# 1-Schematic_Rotopano.net
KiCad netlist of a schematic drawn in EasyEDA
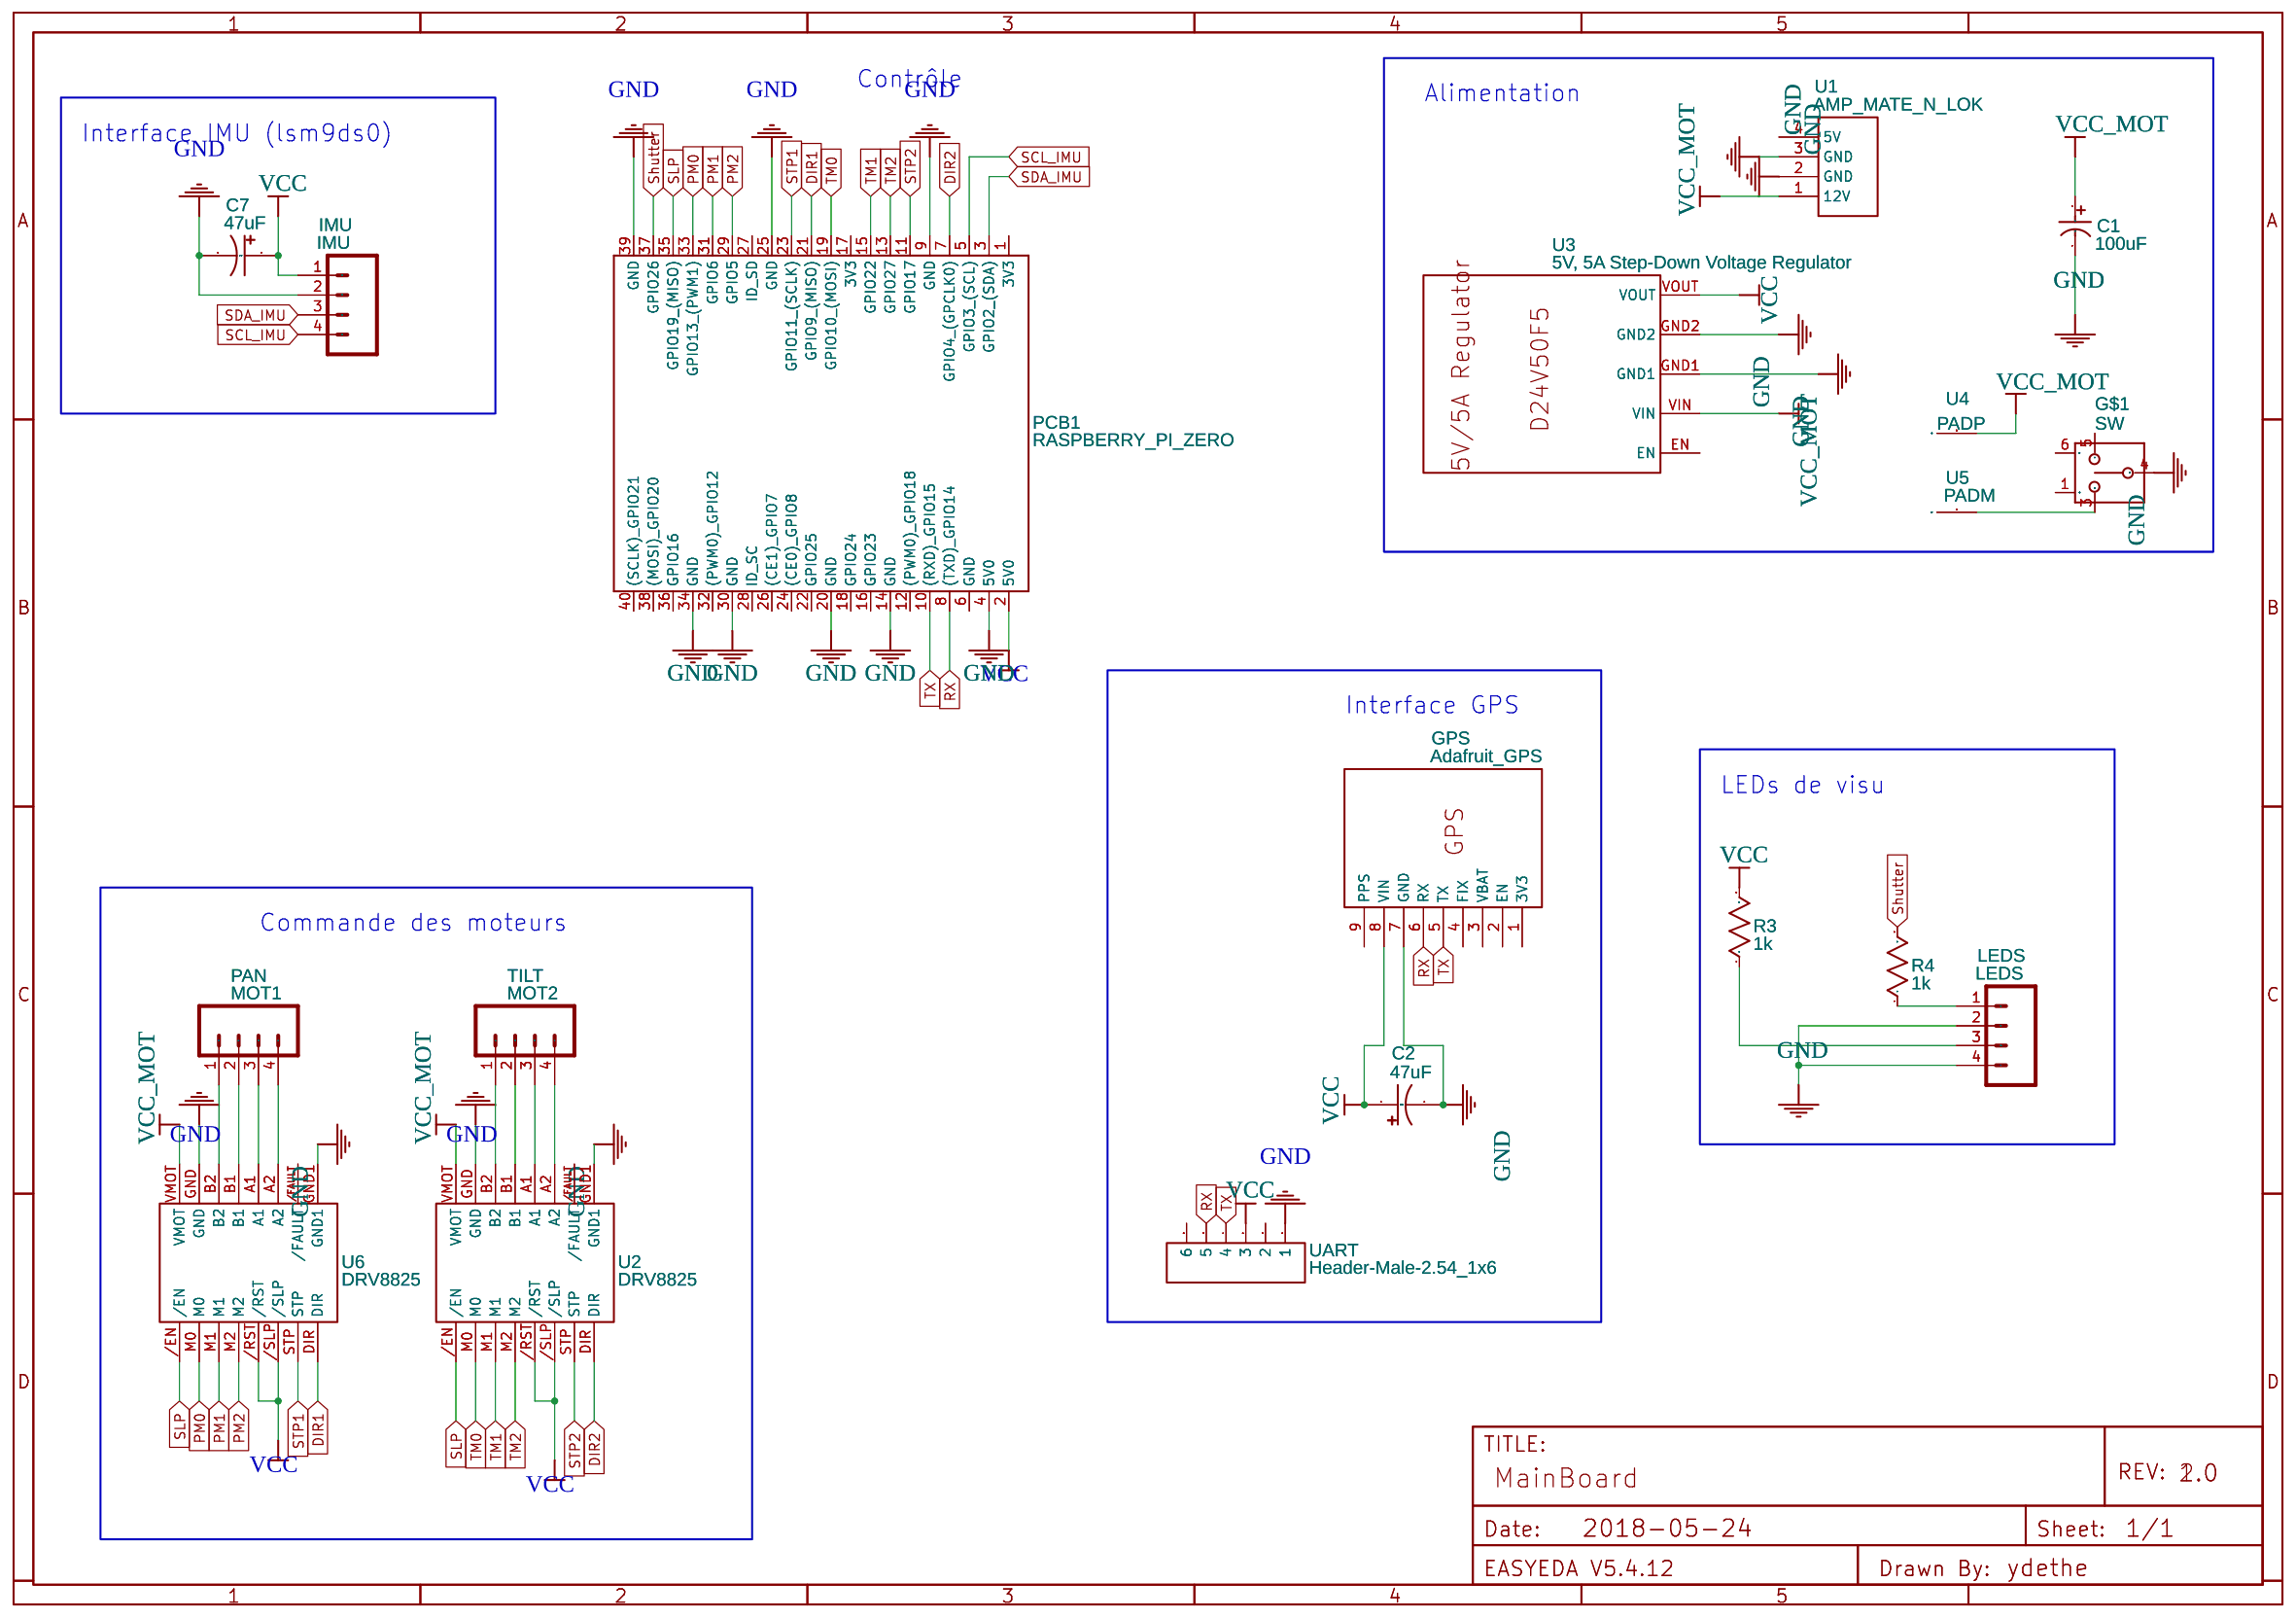
[diagram p0: schematic sheet]

(export (version "E")
  (design (tool "Eeschema 10.0.6"))
  (components
    (comp (ref "C1")
      (value "100uF")
      (fields (field (name "BOM_Manufacturer Part") "100uF 25V") (field (name "BOM_Supplier Part") "C13376"))
      (libsource (lib "") (part "100uF 25V"))
    )
    (comp (ref "C2")
      (value "47uF")
      (fields (field (name "BOM_Manufacturer Part") "?"))
      (libsource (lib "") (part "Cap_Electrolytic(TH)_D6.3XF2.5_US_1"))
    )
    (comp (ref "C7")
      (value "47uF")
      (fields (field (name "BOM_Manufacturer Part") "?"))
      (libsource (lib "") (part "Cap_Electrolytic(TH)_D6.3XF2.5_US"))
    )
    (comp (ref "G$1")
      (value "SW")
      (fields (field (name "BOM_Manufacturer Part") "?"))
      (libsource (lib "") (part "Unknown_840_20"))
    )
    (comp (ref "GPS")
      (value "Adafruit_GPS")
      (fields
        (field (name "BOM_Manufacturer Part") "Adafruit Ultimate GPS Breakout - 66 channel w/10 Hz updates - Version 3")
        (field (name "BOM_Supplier Part") "undefined")
      )
      (libsource (lib "") (part "Unknown_550_180"))
    )
    (comp (ref "IMU")
      (value "IMU")
      (fields (field (name "BOM_Manufacturer Part") "?"))
      (libsource (lib "") (part "Unknown_-50_-60"))
    )
    (comp (ref "LEDS")
      (value "LEDS")
      (fields (field (name "BOM_Manufacturer Part") "?"))
      (libsource (lib "") (part "Unknown_790_310"))
    )
    (comp (ref "PAN")
      (value "MOT1")
      (fields (field (name "BOM_Manufacturer Part") "?"))
      (libsource (lib "") (part "Unknown_-100_320"))
    )
    (comp (ref "PCB1")
      (value "RASPBERRY_PI_ZERO")
      (fields (field (name "BOM_Manufacturer Part") "?"))
      (libsource (lib "") (part "Unknown_200_10"))
    )
    (comp (ref "R3")
      (value "1k")
      (fields (field (name "BOM_Manufacturer Part") "?"))
      (libsource (lib "") (part "Res_AXIAL-0.3(1/8W)_US"))
    )
    (comp (ref "R4")
      (value "1k")
      (fields (field (name "BOM_Manufacturer Part") "?"))
      (libsource (lib "") (part "Res_AXIAL-0.3(1/8W)_US"))
    )
    (comp (ref "TILT")
      (value "MOT2")
      (fields (field (name "BOM_Manufacturer Part") "?"))
      (libsource (lib "") (part "Unknown_40_320"))
    )
    (comp (ref "U1")
      (value "AMP_MATE_N_LOK")
      (fields (field (name "BOM_Manufacturer Part") "350424-1") (field (name "BOM_Supplier Part") "718-9605"))
      (libsource (lib "") (part "Unknown_720_-110"))
    )
    (comp (ref "U2")
      (value "DRV8825")
      (fields (field (name "BOM_Manufacturer Part") "Pololu") (field (name "BOM_Supplier Part") "undefined"))
      (libsource (lib "") (part "Unknown_0_460"))
    )
    (comp (ref "U3")
      (value "5V, 5A Step-Down Voltage Regulator")
      (fields (field (name "BOM_Manufacturer Part") "D24V50F5"))
      (libsource (lib "") (part "Unknown_490_40"))
    )
    (comp (ref "U4")
      (value "PADP")
      (fields (field (name "BOM_Manufacturer Part") "?"))
      (libsource (lib "") (part "Unknown_760_10"))
    )
    (comp (ref "U5")
      (value "PADM")
      (fields (field (name "BOM_Manufacturer Part") "?"))
      (libsource (lib "") (part "Unknown_760_50"))
    )
    (comp (ref "U6")
      (value "DRV8825")
      (fields (field (name "BOM_Manufacturer Part") "Pololu") (field (name "BOM_Supplier Part") "undefined"))
      (libsource (lib "") (part "Unknown_-140_460"))
    )
    (comp (ref "UART")
      (value "Header-Male-2.54_1x6")
      (fields (field (name "BOM_Supplier Part") "C37208"))
      (libsource (lib "") (part "Unknown_400_430"))
    )
  )
  (nets
    (net (code "1") (name "DIR1") (class "Default")
      (node (ref "PCB1") (pin "21") (pinfunction "GPIO9_(MISO)_21") (pintype "unspecified"))
      (node (ref "U6") (pin "DIR") (pinfunction "DIR_DIR") (pintype "unspecified"))
    )
    (net (code "2") (name "DIR2") (class "Default")
      (node (ref "PCB1") (pin "7") (pinfunction "GPIO4_(GPCLK0)_7") (pintype "unspecified"))
      (node (ref "U2") (pin "DIR") (pinfunction "DIR_DIR") (pintype "unspecified"))
    )
    (net (code "3") (name "GND") (class "Default")
      (node (ref "C1") (pin "2") (pinfunction "2_2") (pintype "input"))
      (node (ref "C2") (pin "2") (pinfunction "2_2") (pintype "unspecified"))
      (node (ref "C7") (pin "2") (pinfunction "2_2") (pintype "unspecified"))
      (node (ref "G$1") (pin "4") (pinfunction "2_4") (pintype "bidirectional"))
      (node (ref "GPS") (pin "7") (pinfunction "GND_7") (pintype "unspecified"))
      (node (ref "IMU") (pin "2") (pinfunction "2_2") (pintype "unspecified"))
      (node (ref "LEDS") (pin "2") (pinfunction "2_2") (pintype "unspecified"))
      (node (ref "LEDS") (pin "4") (pinfunction "4_4") (pintype "unspecified"))
      (node (ref "PCB1") (pin "14") (pinfunction "GND_14") (pintype "unspecified"))
      (node (ref "PCB1") (pin "20") (pinfunction "GND_20") (pintype "unspecified"))
      (node (ref "PCB1") (pin "25") (pinfunction "GND_25") (pintype "unspecified"))
      (node (ref "PCB1") (pin "30") (pinfunction "GND_30") (pintype "unspecified"))
      (node (ref "PCB1") (pin "34") (pinfunction "GND_34") (pintype "unspecified"))
      (node (ref "PCB1") (pin "39") (pinfunction "GND_39") (pintype "unspecified"))
      (node (ref "PCB1") (pin "4") (pinfunction "5V0_4") (pintype "unspecified"))
      (node (ref "PCB1") (pin "9") (pinfunction "GND_9") (pintype "unspecified"))
      (node (ref "U1") (pin "2") (pinfunction "GND_2") (pintype "unspecified"))
      (node (ref "U1") (pin "3") (pinfunction "GND_3") (pintype "unspecified"))
      (node (ref "U2") (pin "GND") (pinfunction "GND_GND") (pintype "unspecified"))
      (node (ref "U2") (pin "GND1") (pinfunction "GND1_GND1") (pintype "unspecified"))
      (node (ref "U3") (pin "GND1") (pinfunction "GND1_GND1") (pintype "unspecified"))
      (node (ref "U3") (pin "GND2") (pinfunction "GND2_GND2") (pintype "unspecified"))
      (node (ref "U6") (pin "GND") (pinfunction "GND_GND") (pintype "unspecified"))
      (node (ref "U6") (pin "GND1") (pinfunction "GND1_GND1") (pintype "unspecified"))
      (node (ref "UART") (pin "1") (pinfunction "1_1") (pintype "input"))
    )
    (net (code "4") (name "Net-(G$1-Pad3)") (class "Default")
      (node (ref "G$1") (pin "3") (pinfunction "3_3") (pintype "bidirectional"))
      (node (ref "U5") (pin "P$1") (pinfunction "P$1_P$1") (pintype "unspecified"))
    )
    (net (code "5") (name "Net-(LEDS-Pad1)") (class "Default")
      (node (ref "LEDS") (pin "1") (pinfunction "1_1") (pintype "unspecified"))
      (node (ref "R4") (pin "1") (pinfunction "1_1") (pintype "unspecified"))
    )
    (net (code "6") (name "Net-(LEDS-Pad3)") (class "Default")
      (node (ref "LEDS") (pin "3") (pinfunction "3_3") (pintype "unspecified"))
      (node (ref "R3") (pin "1") (pinfunction "1_1") (pintype "unspecified"))
    )
    (net (code "7") (name "Net-(PAN-Pad1)") (class "Default")
      (node (ref "PAN") (pin "1") (pinfunction "1_1") (pintype "unspecified"))
      (node (ref "U6") (pin "B2") (pinfunction "B2_B2") (pintype "unspecified"))
    )
    (net (code "8") (name "Net-(PAN-Pad2)") (class "Default")
      (node (ref "PAN") (pin "2") (pinfunction "2_2") (pintype "unspecified"))
      (node (ref "U6") (pin "B1") (pinfunction "B1_B1") (pintype "unspecified"))
    )
    (net (code "9") (name "Net-(PAN-Pad3)") (class "Default")
      (node (ref "PAN") (pin "3") (pinfunction "3_3") (pintype "unspecified"))
      (node (ref "U6") (pin "A1") (pinfunction "A1_A1") (pintype "unspecified"))
    )
    (net (code "10") (name "Net-(PAN-Pad4)") (class "Default")
      (node (ref "PAN") (pin "4") (pinfunction "4_4") (pintype "unspecified"))
      (node (ref "U6") (pin "A2") (pinfunction "A2_A2") (pintype "unspecified"))
    )
    (net (code "11") (name "Net-(TILT-Pad1)") (class "Default")
      (node (ref "TILT") (pin "1") (pinfunction "1_1") (pintype "unspecified"))
      (node (ref "U2") (pin "B2") (pinfunction "B2_B2") (pintype "unspecified"))
    )
    (net (code "12") (name "Net-(TILT-Pad2)") (class "Default")
      (node (ref "TILT") (pin "2") (pinfunction "2_2") (pintype "unspecified"))
      (node (ref "U2") (pin "B1") (pinfunction "B1_B1") (pintype "unspecified"))
    )
    (net (code "13") (name "Net-(TILT-Pad3)") (class "Default")
      (node (ref "TILT") (pin "3") (pinfunction "3_3") (pintype "unspecified"))
      (node (ref "U2") (pin "A1") (pinfunction "A1_A1") (pintype "unspecified"))
    )
    (net (code "14") (name "Net-(TILT-Pad4)") (class "Default")
      (node (ref "TILT") (pin "4") (pinfunction "4_4") (pintype "unspecified"))
      (node (ref "U2") (pin "A2") (pinfunction "A2_A2") (pintype "unspecified"))
    )
    (net (code "15") (name "PM0") (class "Default")
      (node (ref "PCB1") (pin "33") (pinfunction "GPIO13_(PWM1)_33") (pintype "unspecified"))
      (node (ref "U6") (pin "M0") (pinfunction "M0_M0") (pintype "unspecified"))
    )
    (net (code "16") (name "PM1") (class "Default")
      (node (ref "PCB1") (pin "31") (pinfunction "GPIO6_31") (pintype "unspecified"))
      (node (ref "U6") (pin "M1") (pinfunction "M1_M1") (pintype "unspecified"))
    )
    (net (code "17") (name "PM2") (class "Default")
      (node (ref "PCB1") (pin "29") (pinfunction "GPIO5_29") (pintype "unspecified"))
      (node (ref "U6") (pin "M2") (pinfunction "M2_M2") (pintype "unspecified"))
    )
    (net (code "18") (name "RX") (class "Default")
      (node (ref "GPS") (pin "6") (pinfunction "RX_6") (pintype "unspecified"))
      (node (ref "PCB1") (pin "8") (pinfunction "(TXD)_GPIO14_8") (pintype "unspecified"))
      (node (ref "UART") (pin "5") (pinfunction "5_5") (pintype "input"))
    )
    (net (code "19") (name "SCL_IMU") (class "Default")
      (node (ref "IMU") (pin "4") (pinfunction "4_4") (pintype "unspecified"))
      (node (ref "PCB1") (pin "5") (pinfunction "GPIO3_(SCL)_5") (pintype "unspecified"))
    )
    (net (code "20") (name "SDA_IMU") (class "Default")
      (node (ref "IMU") (pin "3") (pinfunction "3_3") (pintype "unspecified"))
      (node (ref "PCB1") (pin "3") (pinfunction "GPIO2_(SDA)_3") (pintype "unspecified"))
    )
    (net (code "21") (name "SLP") (class "Default")
      (node (ref "PCB1") (pin "35") (pinfunction "GPIO19_(MISO)_35") (pintype "unspecified"))
      (node (ref "U2") (pin "/EN") (pinfunction "/EN_/EN") (pintype "unspecified"))
      (node (ref "U6") (pin "/EN") (pinfunction "/EN_/EN") (pintype "unspecified"))
    )
    (net (code "22") (name "STP1") (class "Default")
      (node (ref "PCB1") (pin "23") (pinfunction "GPIO11_(SCLK)_23") (pintype "unspecified"))
      (node (ref "U6") (pin "STP") (pinfunction "STP_STP") (pintype "unspecified"))
    )
    (net (code "23") (name "STP2") (class "Default")
      (node (ref "PCB1") (pin "11") (pinfunction "GPIO17_11") (pintype "unspecified"))
      (node (ref "U2") (pin "STP") (pinfunction "STP_STP") (pintype "unspecified"))
    )
    (net (code "24") (name "Shutter") (class "Default")
      (node (ref "PCB1") (pin "37") (pinfunction "GPIO26_37") (pintype "unspecified"))
      (node (ref "R4") (pin "2") (pinfunction "2_2") (pintype "unspecified"))
    )
    (net (code "25") (name "TM0") (class "Default")
      (node (ref "PCB1") (pin "19") (pinfunction "GPIO10_(MOSI)_19") (pintype "unspecified"))
      (node (ref "U2") (pin "M0") (pinfunction "M0_M0") (pintype "unspecified"))
    )
    (net (code "26") (name "TM1") (class "Default")
      (node (ref "PCB1") (pin "15") (pinfunction "GPIO22_15") (pintype "unspecified"))
      (node (ref "U2") (pin "M1") (pinfunction "M1_M1") (pintype "unspecified"))
    )
    (net (code "27") (name "TM2") (class "Default")
      (node (ref "PCB1") (pin "13") (pinfunction "GPIO27_13") (pintype "unspecified"))
      (node (ref "U2") (pin "M2") (pinfunction "M2_M2") (pintype "unspecified"))
    )
    (net (code "28") (name "TX") (class "Default")
      (node (ref "GPS") (pin "5") (pinfunction "TX_5") (pintype "unspecified"))
      (node (ref "PCB1") (pin "10") (pinfunction "(RXD)_GPIO15_10") (pintype "unspecified"))
      (node (ref "UART") (pin "4") (pinfunction "4_4") (pintype "input"))
    )
    (net (code "29") (name "VCC") (class "Default")
      (node (ref "C2") (pin "1") (pinfunction "1_1") (pintype "unspecified"))
      (node (ref "C7") (pin "1") (pinfunction "1_1") (pintype "unspecified"))
      (node (ref "GPS") (pin "8") (pinfunction "VIN_8") (pintype "unspecified"))
      (node (ref "IMU") (pin "1") (pinfunction "1_1") (pintype "unspecified"))
      (node (ref "PCB1") (pin "2") (pinfunction "5V0_2") (pintype "unspecified"))
      (node (ref "R3") (pin "2") (pinfunction "2_2") (pintype "unspecified"))
      (node (ref "U2") (pin "/RST") (pinfunction "/RST_/RST") (pintype "unspecified"))
      (node (ref "U2") (pin "/SLP") (pinfunction "/SLP_/SLP") (pintype "unspecified"))
      (node (ref "U3") (pin "VOUT") (pinfunction "VOUT_VOUT") (pintype "unspecified"))
      (node (ref "U6") (pin "/RST") (pinfunction "/RST_/RST") (pintype "unspecified"))
      (node (ref "U6") (pin "/SLP") (pinfunction "/SLP_/SLP") (pintype "unspecified"))
      (node (ref "UART") (pin "3") (pinfunction "3_3") (pintype "input"))
    )
    (net (code "30") (name "VCC_MOT") (class "Default")
      (node (ref "C1") (pin "1") (pinfunction "1_1") (pintype "input"))
      (node (ref "U1") (pin "1") (pinfunction "12V_1") (pintype "unspecified"))
      (node (ref "U2") (pin "VMOT") (pinfunction "VMOT_VMOT") (pintype "unspecified"))
      (node (ref "U3") (pin "VIN") (pinfunction "VIN_VIN") (pintype "unspecified"))
      (node (ref "U4") (pin "P$1") (pinfunction "P$1_P$1") (pintype "unspecified"))
      (node (ref "U6") (pin "VMOT") (pinfunction "VMOT_VMOT") (pintype "unspecified"))
    )
    (net (code "31") (name "unconnected-(G$1-1-Pad5)") (class "Default")
      (node (ref "G$1") (pin "5") (pinfunction "1_5") (pintype "bidirectional"))
    )
    (net (code "32") (name "unconnected-(G$1-G1-Pad6)") (class "Default")
      (node (ref "G$1") (pin "6") (pinfunction "G1_6") (pintype "bidirectional"))
    )
    (net (code "33") (name "unconnected-(G$1-G2-Pad1)") (class "Default")
      (node (ref "G$1") (pin "1") (pinfunction "G2_1") (pintype "bidirectional"))
    )
    (net (code "34") (name "unconnected-(GPS-3V3-Pad1)") (class "Default")
      (node (ref "GPS") (pin "1") (pinfunction "3V3_1") (pintype "passive"))
    )
    (net (code "35") (name "unconnected-(GPS-EN-Pad2)") (class "Default")
      (node (ref "GPS") (pin "2") (pinfunction "EN_2") (pintype "unspecified"))
    )
    (net (code "36") (name "unconnected-(GPS-FIX-Pad4)") (class "Default")
      (node (ref "GPS") (pin "4") (pinfunction "FIX_4") (pintype "unspecified"))
    )
    (net (code "37") (name "unconnected-(GPS-PPS-Pad9)") (class "Default")
      (node (ref "GPS") (pin "9") (pinfunction "PPS_9") (pintype "unspecified"))
    )
    (net (code "38") (name "unconnected-(GPS-VBAT-Pad3)") (class "Default")
      (node (ref "GPS") (pin "3") (pinfunction "VBAT_3") (pintype "unspecified"))
    )
    (net (code "39") (name "unconnected-(PCB1-(CE0)_GPIO8-Pad24)") (class "Default")
      (node (ref "PCB1") (pin "24") (pinfunction "(CE0)_GPIO8_24") (pintype "unspecified"))
    )
    (net (code "40") (name "unconnected-(PCB1-(CE1)_GPIO7-Pad26)") (class "Default")
      (node (ref "PCB1") (pin "26") (pinfunction "(CE1)_GPIO7_26") (pintype "unspecified"))
    )
    (net (code "41") (name "unconnected-(PCB1-(MOSI)_GPIO20-Pad38)") (class "Default")
      (node (ref "PCB1") (pin "38") (pinfunction "(MOSI)_GPIO20_38") (pintype "unspecified"))
    )
    (net (code "42") (name "unconnected-(PCB1-(PWM0)_GPIO12-Pad32)") (class "Default")
      (node (ref "PCB1") (pin "32") (pinfunction "(PWM0)_GPIO12_32") (pintype "unspecified"))
    )
    (net (code "43") (name "unconnected-(PCB1-(PWM0)_GPIO18-Pad12)") (class "Default")
      (node (ref "PCB1") (pin "12") (pinfunction "(PWM0)_GPIO18_12") (pintype "unspecified"))
    )
    (net (code "44") (name "unconnected-(PCB1-(SCLK)_GPIO21-Pad40)") (class "Default")
      (node (ref "PCB1") (pin "40") (pinfunction "(SCLK)_GPIO21_40") (pintype "unspecified"))
    )
    (net (code "45") (name "unconnected-(PCB1-3V3-Pad1)") (class "Default")
      (node (ref "PCB1") (pin "1") (pinfunction "3V3_1") (pintype "unspecified"))
    )
    (net (code "46") (name "unconnected-(PCB1-3V3-Pad17)") (class "Default")
      (node (ref "PCB1") (pin "17") (pinfunction "3V3_17") (pintype "unspecified"))
    )
    (net (code "47") (name "unconnected-(PCB1-GND-Pad6)") (class "Default")
      (node (ref "PCB1") (pin "6") (pinfunction "GND_6") (pintype "unspecified"))
    )
    (net (code "48") (name "unconnected-(PCB1-GPIO16-Pad36)") (class "Default")
      (node (ref "PCB1") (pin "36") (pinfunction "GPIO16_36") (pintype "unspecified"))
    )
    (net (code "49") (name "unconnected-(PCB1-GPIO23-Pad16)") (class "Default")
      (node (ref "PCB1") (pin "16") (pinfunction "GPIO23_16") (pintype "unspecified"))
    )
    (net (code "50") (name "unconnected-(PCB1-GPIO24-Pad18)") (class "Default")
      (node (ref "PCB1") (pin "18") (pinfunction "GPIO24_18") (pintype "unspecified"))
    )
    (net (code "51") (name "unconnected-(PCB1-GPIO25-Pad22)") (class "Default")
      (node (ref "PCB1") (pin "22") (pinfunction "GPIO25_22") (pintype "unspecified"))
    )
    (net (code "52") (name "unconnected-(PCB1-ID_SC-Pad28)") (class "Default")
      (node (ref "PCB1") (pin "28") (pinfunction "ID_SC_28") (pintype "unspecified"))
    )
    (net (code "53") (name "unconnected-(PCB1-ID_SD-Pad27)") (class "Default")
      (node (ref "PCB1") (pin "27") (pinfunction "ID_SD_27") (pintype "unspecified"))
    )
    (net (code "54") (name "unconnected-(U1-5V-Pad4)") (class "Default")
      (node (ref "U1") (pin "4") (pinfunction "5V_4") (pintype "unspecified"))
    )
    (net (code "55") (name "unconnected-(U2-Pad{slash}FAULT)") (class "Default")
      (node (ref "U2") (pin "/FAULT") (pinfunction "/FAULT_/FAULT") (pintype "unspecified"))
    )
    (net (code "56") (name "unconnected-(U3-PadEN)") (class "Default")
      (node (ref "U3") (pin "EN") (pinfunction "EN_EN") (pintype "unspecified"))
    )
    (net (code "57") (name "unconnected-(U6-Pad{slash}FAULT)") (class "Default")
      (node (ref "U6") (pin "/FAULT") (pinfunction "/FAULT_/FAULT") (pintype "unspecified"))
    )
    (net (code "58") (name "unconnected-(UART-Pad2)") (class "Default")
      (node (ref "UART") (pin "2") (pinfunction "2_2") (pintype "input"))
    )
    (net (code "59") (name "unconnected-(UART-Pad6)") (class "Default")
      (node (ref "UART") (pin "6") (pinfunction "6_6") (pintype "input"))
    )
  )
)
